# ppgimp.net
KiCad netlist of a schematic drawn in EAGLE
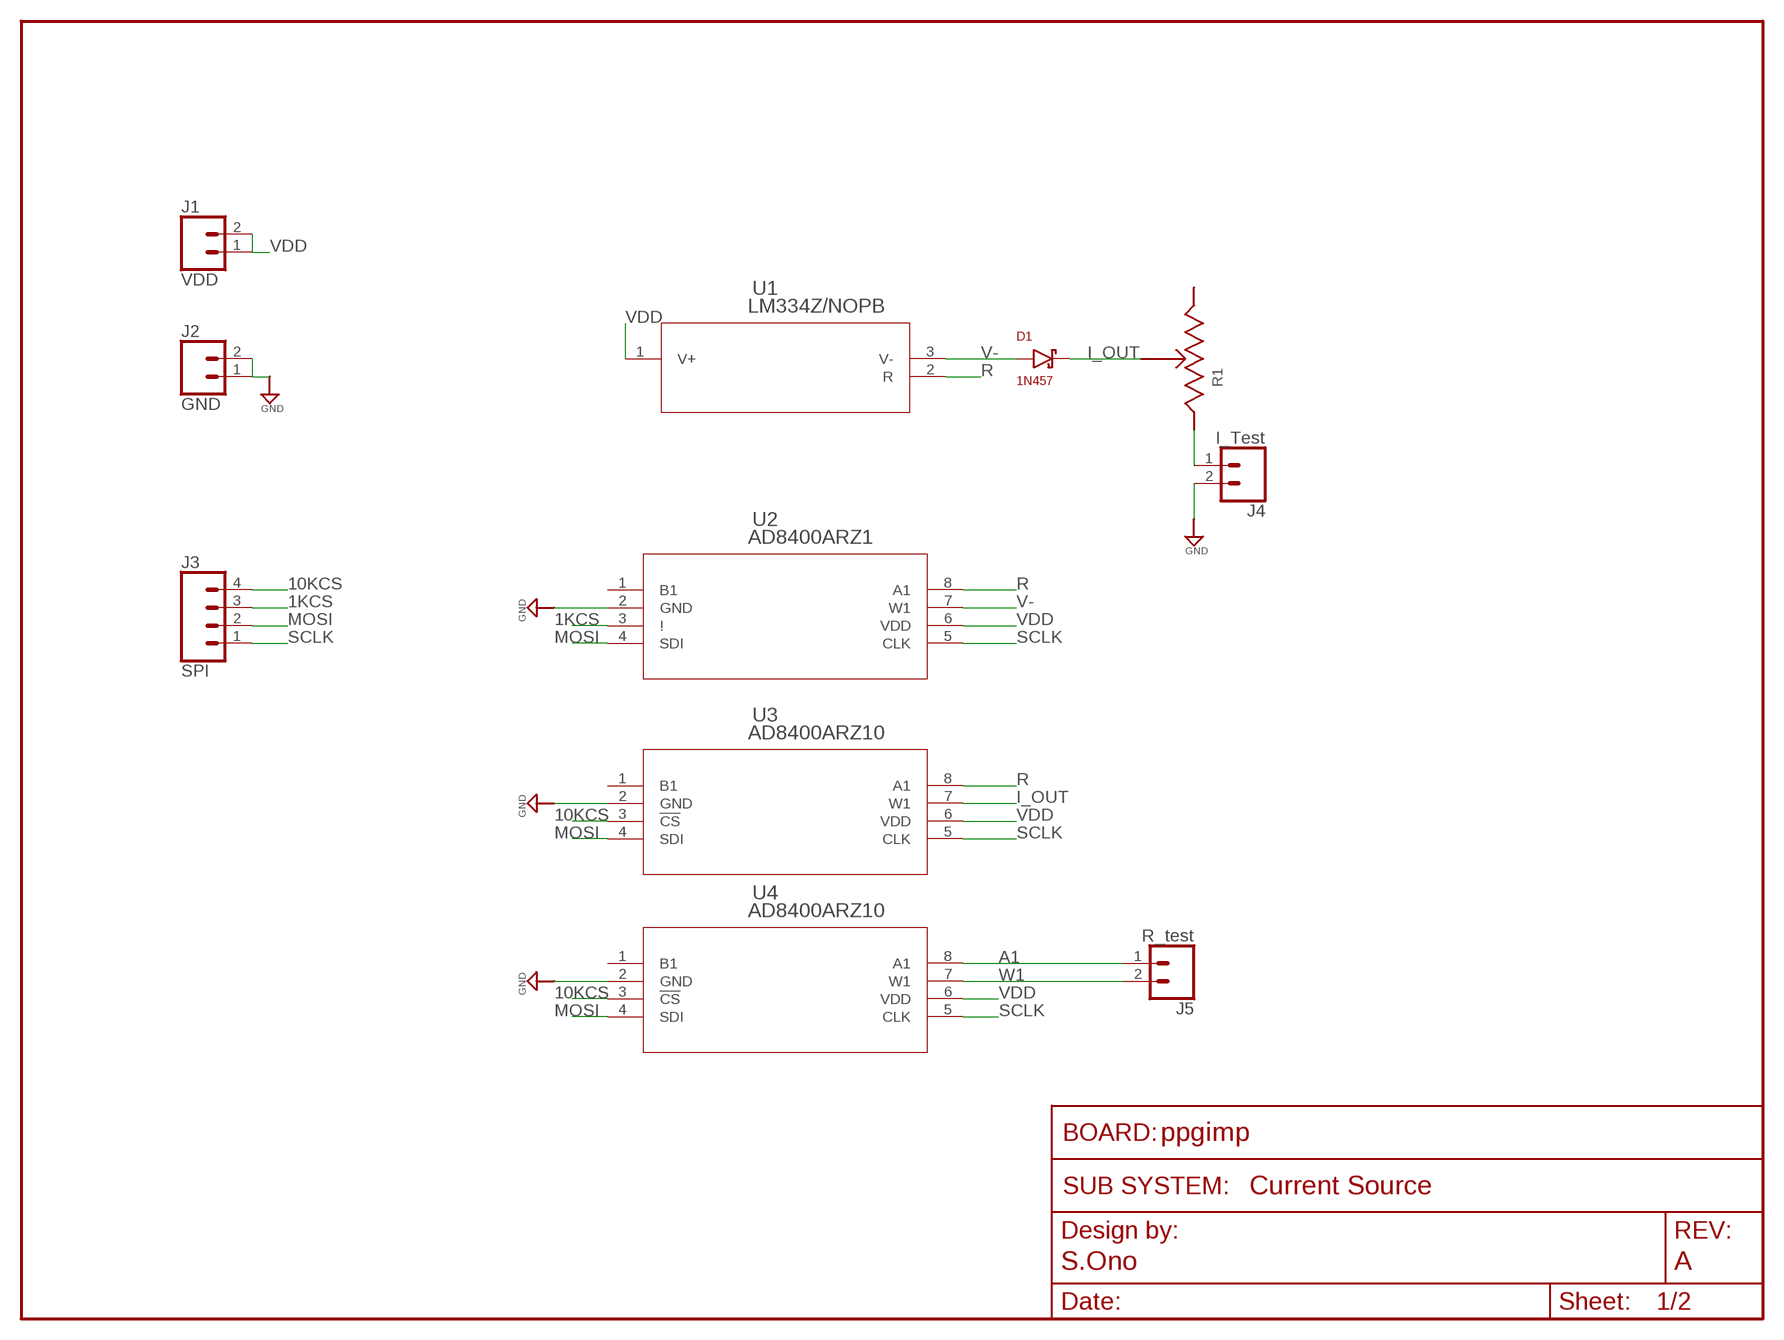
[diagram p0: schematic, sheet 1]
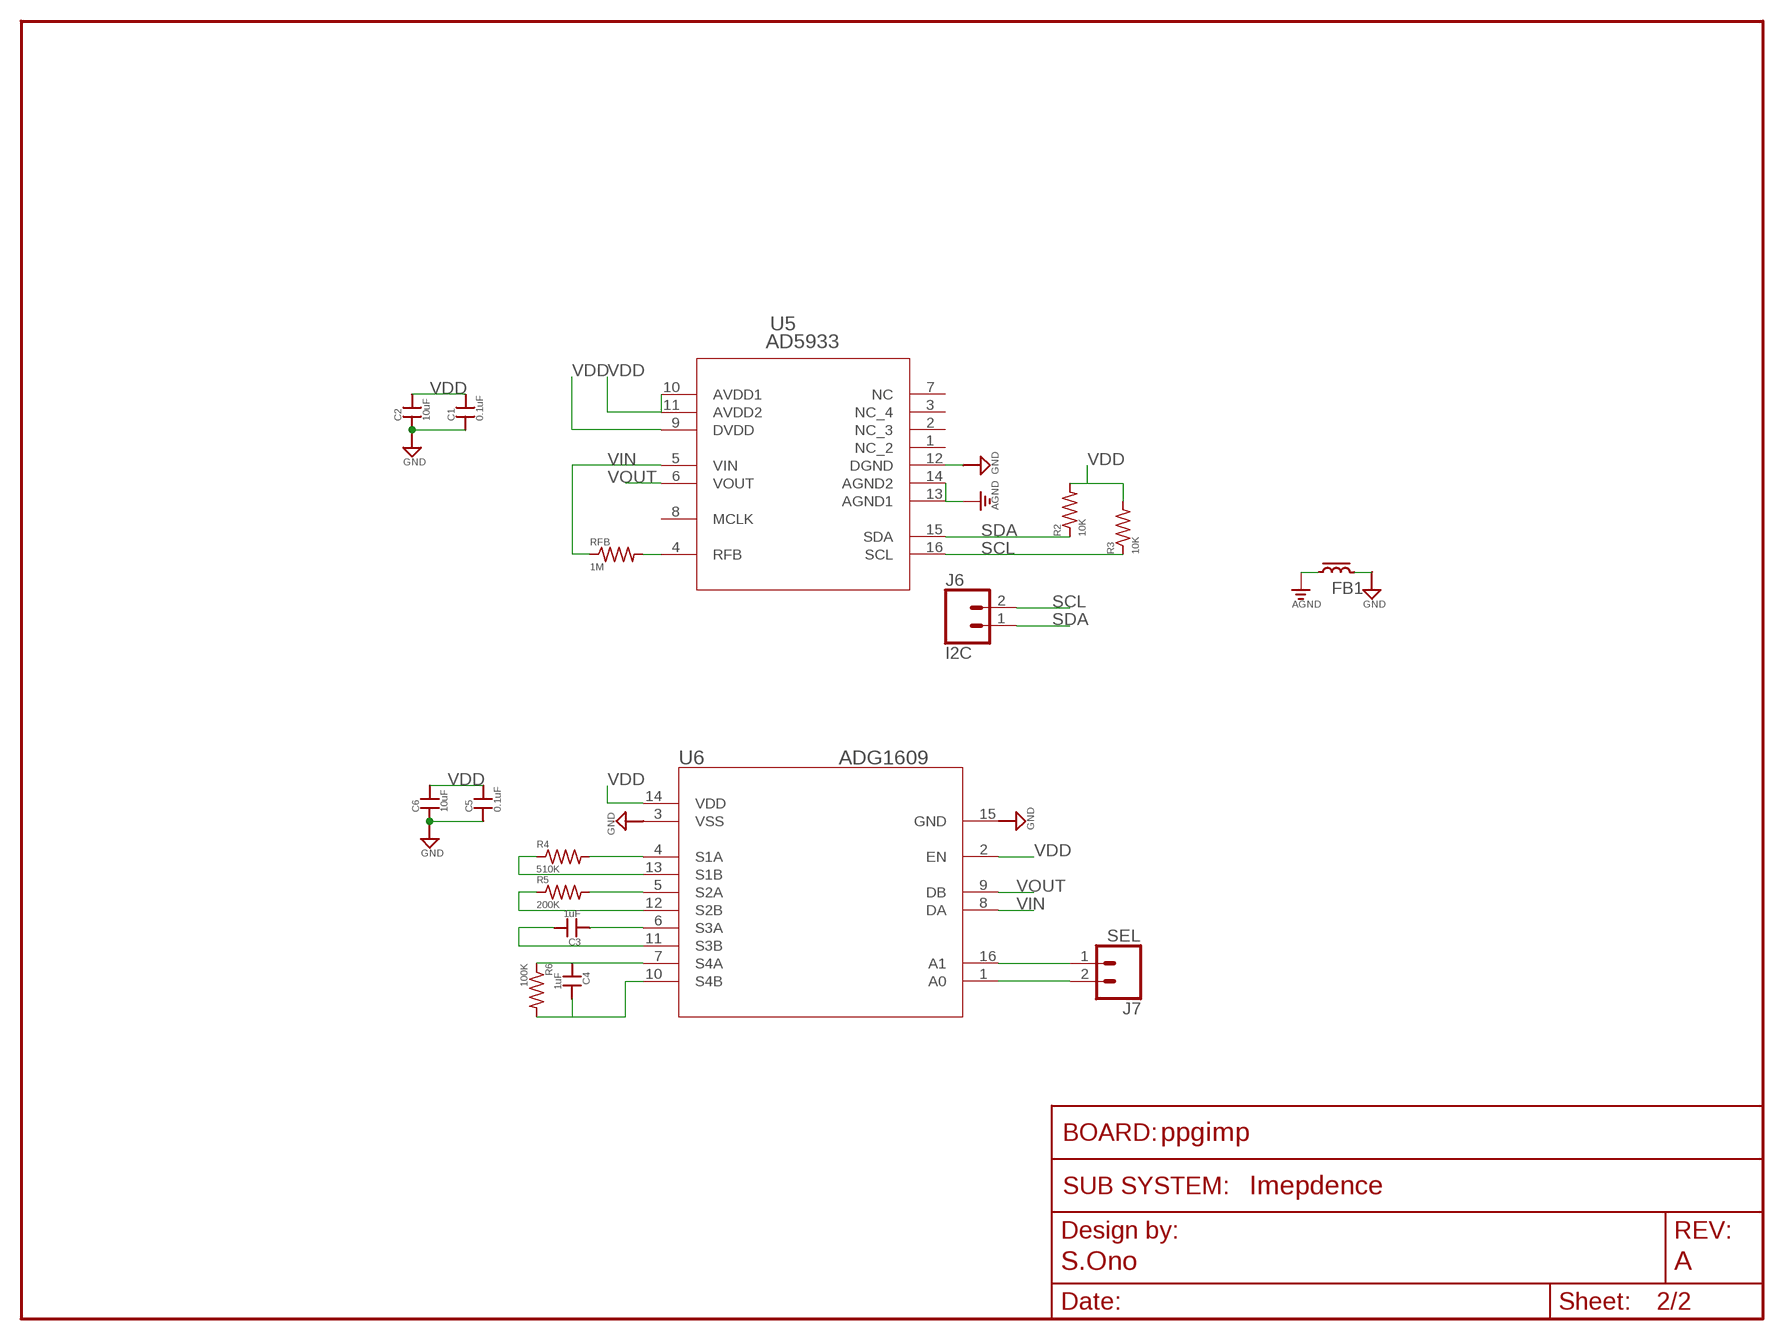
[diagram p1: schematic, sheet 2]

(export (version "E")
  (design (tool "Eeschema 10.0.6"))
  (components
    (comp (ref "C1")
      (value "0.1uF")
      (footprint "eagle-import:0603-CAP")
      (libsource (lib "eagle-import") (part "CAP0603-CAP"))
    )
    (comp (ref "C2")
      (value "10uF")
      (footprint "eagle-import:0603-CAP")
      (libsource (lib "eagle-import") (part "CAP0603-CAP"))
    )
    (comp (ref "C3")
      (value "1uF")
      (footprint "eagle-import:0603-CAP")
      (libsource (lib "eagle-import") (part "CAP0603-CAP"))
    )
    (comp (ref "C4")
      (value "1uF")
      (footprint "eagle-import:0603-CAP")
      (libsource (lib "eagle-import") (part "CAP0603-CAP"))
    )
    (comp (ref "C5")
      (value "0.1uF")
      (footprint "eagle-import:0603-CAP")
      (libsource (lib "eagle-import") (part "CAP0603-CAP"))
    )
    (comp (ref "C6")
      (value "10uF")
      (footprint "eagle-import:0603-CAP")
      (libsource (lib "eagle-import") (part "CAP0603-CAP"))
    )
    (comp (ref "FB1")
      (value "FERRITE")
      (footprint "eagle-import:0603-FERR")
      (libsource (lib "eagle-import") (part "FERRITE"))
    )
    (comp (ref "J6")
      (value "I2C")
      (footprint "eagle-import:1X02")
      (libsource (lib "eagle-import") (part "CONN_02"))
    )
    (comp (ref "J7")
      (value "SEL")
      (footprint "eagle-import:1X02")
      (libsource (lib "eagle-import") (part "CONN_02"))
    )
    (comp (ref "R2")
      (value "10K")
      (footprint "eagle-import:R0603")
      (fields (field (name "MANUFACTURER") "Rohm Semiconductor"))
      (libsource (lib "eagle-import") (part "R-US_R0603"))
    )
    (comp (ref "R3")
      (value "10K")
      (footprint "eagle-import:R0603")
      (fields (field (name "MANUFACTURER") "Rohm Semiconductor"))
      (libsource (lib "eagle-import") (part "R-US_R0603"))
    )
    (comp (ref "R4")
      (value "510K")
      (footprint "eagle-import:R0603")
      (fields (field (name "MANUFACTURER") "Rohm Semiconductor"))
      (libsource (lib "eagle-import") (part "R-US_R0603"))
    )
    (comp (ref "R5")
      (value "200K")
      (footprint "eagle-import:R0603")
      (fields (field (name "MANUFACTURER") "Rohm Semiconductor"))
      (libsource (lib "eagle-import") (part "R-US_R0603"))
    )
    (comp (ref "R6")
      (value "100K")
      (footprint "eagle-import:R0603")
      (fields (field (name "MANUFACTURER") "Rohm Semiconductor"))
      (libsource (lib "eagle-import") (part "R-US_R0603"))
    )
    (comp (ref "RFB")
      (value "1M")
      (footprint "eagle-import:R0603")
      (fields (field (name "MANUFACTURER") "Rohm Semiconductor"))
      (libsource (lib "eagle-import") (part "R-US_R0603"))
    )
    (comp (ref "U5")
      (value "AD5933")
      (footprint "eagle-import:RS_16")
      (fields (field (name "MANUFACTURER_PART_NUMBER") "AD5933YRSZ"))
      (libsource (lib "eagle-import") (part "AD5933YRSZ"))
    )
    (comp (ref "U6")
      (value "ADG1609")
      (footprint "eagle-import:RU_16")
      (fields (field (name "MANUFACTURER_PART_NUMBER") "ADG1609BRUZ"))
      (libsource (lib "eagle-import") (part "ADG1609"))
    )
    (comp (ref "D1")
      (value "1N457")
      (footprint "eagle-import:DIODE_THRU")
      (libsource (lib "eagle-import") (part "1N457"))
    )
    (comp (ref "J1")
      (value "VDD")
      (footprint "eagle-import:1X02")
      (libsource (lib "eagle-import") (part "CONN_02"))
    )
    (comp (ref "J2")
      (value "GND")
      (footprint "eagle-import:1X02")
      (libsource (lib "eagle-import") (part "CONN_02"))
    )
    (comp (ref "J3")
      (value "SPI")
      (footprint "eagle-import:1X04")
      (libsource (lib "eagle-import") (part "CONN_04"))
    )
    (comp (ref "J4")
      (value "I_Test")
      (footprint "eagle-import:1X02")
      (libsource (lib "eagle-import") (part "CONN_02"))
    )
    (comp (ref "J5")
      (value "R_test")
      (footprint "eagle-import:1X02")
      (libsource (lib "eagle-import") (part "CONN_02"))
    )
    (comp (ref "R1")
      (value "POT-3PIN")
      (footprint "eagle-import:POT-3PIN")
      (libsource (lib "eagle-import") (part "POT-3PIN"))
    )
    (comp (ref "U1")
      (value "LM334Z/NOPB")
      (footprint "eagle-import:Z03A")
      (fields (field (name "MANUFACTURER_PART_NUMBER") "LM334ZNOPB"))
      (libsource (lib "eagle-import") (part "LM334Z/NOPB"))
    )
    (comp (ref "U2")
      (value "AD8400ARZ1")
      (footprint "eagle-import:R_8")
      (libsource (lib "eagle-import") (part "AD8400ARZ1"))
    )
    (comp (ref "U3")
      (value "AD8400ARZ10")
      (footprint "eagle-import:R_8")
      (libsource (lib "eagle-import") (part "AD8400ARZ10"))
    )
    (comp (ref "U4")
      (value "AD8400ARZ10")
      (footprint "eagle-import:R_8")
      (libsource (lib "eagle-import") (part "AD8400ARZ10"))
    )
  )
  (nets
    (net (code "1") (name "1KCS") (class "Default")
      (node (ref "J3") (pin "3") (pinfunction "3_3") (pintype "passive"))
      (node (ref "U2") (pin "3") (pinfunction "~_3") (pintype "passive"))
    )
    (net (code "2") (name "10KCS") (class "Default")
      (node (ref "J3") (pin "4") (pinfunction "4_4") (pintype "passive"))
      (node (ref "U3") (pin "3") (pinfunction "~{CS}_3") (pintype "passive"))
      (node (ref "U4") (pin "3") (pinfunction "~{CS}_3") (pintype "passive"))
    )
    (net (code "3") (name "A1") (class "Default")
      (node (ref "J5") (pin "1") (pinfunction "1_1") (pintype "passive"))
      (node (ref "U4") (pin "8") (pinfunction "A1_8") (pintype "passive"))
    )
    (net (code "4") (name "AGND") (class "Default")
      (node (ref "FB1") (pin "1") (pinfunction "P$1_1") (pintype "passive"))
      (node (ref "U5") (pin "13") (pinfunction "AGND1_13") (pintype "passive"))
      (node (ref "U5") (pin "14") (pinfunction "AGND2_14") (pintype "passive"))
    )
    (net (code "5") (name "GND") (class "Default")
      (node (ref "C1") (pin "1") (pinfunction "1_1") (pintype "passive"))
      (node (ref "C2") (pin "1") (pinfunction "1_1") (pintype "passive"))
      (node (ref "C5") (pin "1") (pinfunction "1_1") (pintype "passive"))
      (node (ref "C6") (pin "1") (pinfunction "1_1") (pintype "passive"))
      (node (ref "FB1") (pin "2") (pinfunction "P$2_2") (pintype "passive"))
      (node (ref "J2") (pin "1") (pinfunction "1_1") (pintype "passive"))
      (node (ref "J2") (pin "2") (pinfunction "2_2") (pintype "passive"))
      (node (ref "J4") (pin "2") (pinfunction "2_2") (pintype "passive"))
      (node (ref "U2") (pin "2") (pinfunction "GND_2") (pintype "passive"))
      (node (ref "U3") (pin "2") (pinfunction "GND_2") (pintype "passive"))
      (node (ref "U4") (pin "2") (pinfunction "GND_2") (pintype "passive"))
      (node (ref "U5") (pin "12") (pinfunction "DGND_12") (pintype "passive"))
      (node (ref "U6") (pin "15") (pinfunction "GND_15") (pintype "passive"))
      (node (ref "U6") (pin "3") (pinfunction "VSS_3") (pintype "passive"))
    )
    (net (code "6") (name "I_OUT") (class "Default")
      (node (ref "D1") (pin "2") (pinfunction "N_2") (pintype "bidirectional"))
      (node (ref "R1") (pin "2") (pinfunction "2_2") (pintype "bidirectional"))
      (node (ref "U3") (pin "7") (pinfunction "W1_7") (pintype "passive"))
    )
    (net (code "7") (name "MOSI") (class "Default")
      (node (ref "J3") (pin "2") (pinfunction "2_2") (pintype "passive"))
      (node (ref "U2") (pin "4") (pinfunction "SDI_4") (pintype "passive"))
      (node (ref "U3") (pin "4") (pinfunction "SDI_4") (pintype "passive"))
      (node (ref "U4") (pin "4") (pinfunction "SDI_4") (pintype "passive"))
    )
    (net (code "8") (name "Net-(J4-Pad1)") (class "Default")
      (node (ref "J4") (pin "1") (pinfunction "1_1") (pintype "passive"))
      (node (ref "R1") (pin "3") (pinfunction "3_3") (pintype "bidirectional"))
    )
    (net (code "9") (name "Net-(U5-RFB)") (class "Default")
      (node (ref "RFB") (pin "2") (pinfunction "2_2") (pintype "passive"))
      (node (ref "U5") (pin "4") (pinfunction "RFB_4") (pintype "passive"))
    )
    (net (code "10") (name "Net-(U6-A0)") (class "Default")
      (node (ref "J7") (pin "2") (pinfunction "2_2") (pintype "passive"))
      (node (ref "U6") (pin "1") (pinfunction "A0_1") (pintype "passive"))
    )
    (net (code "11") (name "Net-(U6-A1)") (class "Default")
      (node (ref "J7") (pin "1") (pinfunction "1_1") (pintype "passive"))
      (node (ref "U6") (pin "16") (pinfunction "A1_16") (pintype "passive"))
    )
    (net (code "12") (name "Net-(U6-S1A)") (class "Default")
      (node (ref "R4") (pin "2") (pinfunction "2_2") (pintype "passive"))
      (node (ref "U6") (pin "4") (pinfunction "S1A_4") (pintype "passive"))
    )
    (net (code "13") (name "Net-(U6-S1B)") (class "Default")
      (node (ref "R4") (pin "1") (pinfunction "1_1") (pintype "passive"))
      (node (ref "U6") (pin "13") (pinfunction "S1B_13") (pintype "passive"))
    )
    (net (code "14") (name "Net-(U6-S2A)") (class "Default")
      (node (ref "R5") (pin "2") (pinfunction "2_2") (pintype "passive"))
      (node (ref "U6") (pin "5") (pinfunction "S2A_5") (pintype "passive"))
    )
    (net (code "15") (name "Net-(U6-S2B)") (class "Default")
      (node (ref "R5") (pin "1") (pinfunction "1_1") (pintype "passive"))
      (node (ref "U6") (pin "12") (pinfunction "S2B_12") (pintype "passive"))
    )
    (net (code "16") (name "Net-(U6-S3A)") (class "Default")
      (node (ref "C3") (pin "1") (pinfunction "1_1") (pintype "passive"))
      (node (ref "U6") (pin "6") (pinfunction "S3A_6") (pintype "passive"))
    )
    (net (code "17") (name "Net-(U6-S3B)") (class "Default")
      (node (ref "C3") (pin "2") (pinfunction "2_2") (pintype "passive"))
      (node (ref "U6") (pin "11") (pinfunction "S3B_11") (pintype "passive"))
    )
    (net (code "18") (name "Net-(U6-S4A)") (class "Default")
      (node (ref "C4") (pin "1") (pinfunction "1_1") (pintype "passive"))
      (node (ref "R6") (pin "1") (pinfunction "1_1") (pintype "passive"))
      (node (ref "U6") (pin "7") (pinfunction "S4A_7") (pintype "passive"))
    )
    (net (code "19") (name "Net-(U6-S4B)") (class "Default")
      (node (ref "C4") (pin "2") (pinfunction "2_2") (pintype "passive"))
      (node (ref "R6") (pin "2") (pinfunction "2_2") (pintype "passive"))
      (node (ref "U6") (pin "10") (pinfunction "S4B_10") (pintype "passive"))
    )
    (net (code "20") (name "R") (class "Default")
      (node (ref "U1") (pin "2") (pinfunction "R_2") (pintype "input"))
      (node (ref "U2") (pin "8") (pinfunction "A1_8") (pintype "passive"))
      (node (ref "U3") (pin "8") (pinfunction "A1_8") (pintype "passive"))
    )
    (net (code "21") (name "SCL") (class "Default")
      (node (ref "J6") (pin "2") (pinfunction "2_2") (pintype "passive"))
      (node (ref "R3") (pin "1") (pinfunction "1_1") (pintype "passive"))
      (node (ref "U5") (pin "16") (pinfunction "SCL_16") (pintype "passive"))
    )
    (net (code "22") (name "SCLK") (class "Default")
      (node (ref "J3") (pin "1") (pinfunction "1_1") (pintype "passive"))
      (node (ref "U2") (pin "5") (pinfunction "CLK_5") (pintype "passive"))
      (node (ref "U3") (pin "5") (pinfunction "CLK_5") (pintype "passive"))
      (node (ref "U4") (pin "5") (pinfunction "CLK_5") (pintype "passive"))
    )
    (net (code "23") (name "SDA") (class "Default")
      (node (ref "J6") (pin "1") (pinfunction "1_1") (pintype "passive"))
      (node (ref "R2") (pin "1") (pinfunction "1_1") (pintype "passive"))
      (node (ref "U5") (pin "15") (pinfunction "SDA_15") (pintype "passive"))
    )
    (net (code "24") (name "V-") (class "Default")
      (node (ref "D1") (pin "1") (pinfunction "P_1") (pintype "bidirectional"))
      (node (ref "U1") (pin "3") (pinfunction "V-_3") (pintype "power_in"))
      (node (ref "U2") (pin "7") (pinfunction "W1_7") (pintype "passive"))
    )
    (net (code "25") (name "VDD") (class "Default")
      (node (ref "C1") (pin "2") (pinfunction "2_2") (pintype "passive"))
      (node (ref "C2") (pin "2") (pinfunction "2_2") (pintype "passive"))
      (node (ref "C5") (pin "2") (pinfunction "2_2") (pintype "passive"))
      (node (ref "C6") (pin "2") (pinfunction "2_2") (pintype "passive"))
      (node (ref "J1") (pin "1") (pinfunction "1_1") (pintype "passive"))
      (node (ref "J1") (pin "2") (pinfunction "2_2") (pintype "passive"))
      (node (ref "R2") (pin "2") (pinfunction "2_2") (pintype "passive"))
      (node (ref "R3") (pin "2") (pinfunction "2_2") (pintype "passive"))
      (node (ref "U1") (pin "1") (pinfunction "V+_1") (pintype "power_in"))
      (node (ref "U2") (pin "6") (pinfunction "VDD_6") (pintype "power_in"))
      (node (ref "U3") (pin "6") (pinfunction "VDD_6") (pintype "power_in"))
      (node (ref "U4") (pin "6") (pinfunction "VDD_6") (pintype "power_in"))
      (node (ref "U5") (pin "10") (pinfunction "AVDD1_10") (pintype "passive"))
      (node (ref "U5") (pin "11") (pinfunction "AVDD2_11") (pintype "passive"))
      (node (ref "U5") (pin "9") (pinfunction "DVDD_9") (pintype "passive"))
      (node (ref "U6") (pin "14") (pinfunction "VDD_14") (pintype "passive"))
      (node (ref "U6") (pin "2") (pinfunction "EN_2") (pintype "passive"))
    )
    (net (code "26") (name "VIN") (class "Default")
      (node (ref "RFB") (pin "1") (pinfunction "1_1") (pintype "passive"))
      (node (ref "U5") (pin "5") (pinfunction "VIN_5") (pintype "passive"))
      (node (ref "U6") (pin "8") (pinfunction "DA_8") (pintype "passive"))
    )
    (net (code "27") (name "VOUT") (class "Default")
      (node (ref "U5") (pin "6") (pinfunction "VOUT_6") (pintype "passive"))
      (node (ref "U6") (pin "9") (pinfunction "DB_9") (pintype "passive"))
    )
    (net (code "28") (name "W1") (class "Default")
      (node (ref "J5") (pin "2") (pinfunction "2_2") (pintype "passive"))
      (node (ref "U4") (pin "7") (pinfunction "W1_7") (pintype "passive"))
    )
    (net (code "29") (name "unconnected-(R1-Pad1)") (class "Default")
      (node (ref "R1") (pin "1") (pinfunction "1_1") (pintype "bidirectional"))
    )
    (net (code "30") (name "unconnected-(U2-B1-Pad1)") (class "Default")
      (node (ref "U2") (pin "1") (pinfunction "B1_1") (pintype "passive"))
    )
    (net (code "31") (name "unconnected-(U3-B1-Pad1)") (class "Default")
      (node (ref "U3") (pin "1") (pinfunction "B1_1") (pintype "passive"))
    )
    (net (code "32") (name "unconnected-(U4-B1-Pad1)") (class "Default")
      (node (ref "U4") (pin "1") (pinfunction "B1_1") (pintype "passive"))
    )
    (net (code "33") (name "unconnected-(U5-MCLK-Pad8)") (class "Default")
      (node (ref "U5") (pin "8") (pinfunction "MCLK_8") (pintype "passive"))
    )
    (net (code "34") (name "unconnected-(U5-NC-Pad7)") (class "Default")
      (node (ref "U5") (pin "7") (pinfunction "NC_7") (pintype "passive"))
    )
    (net (code "35") (name "unconnected-(U5-NC_2-Pad1)") (class "Default")
      (node (ref "U5") (pin "1") (pinfunction "NC_2_1") (pintype "passive"))
    )
    (net (code "36") (name "unconnected-(U5-NC_3-Pad2)") (class "Default")
      (node (ref "U5") (pin "2") (pinfunction "NC_3_2") (pintype "passive"))
    )
    (net (code "37") (name "unconnected-(U5-NC_4-Pad3)") (class "Default")
      (node (ref "U5") (pin "3") (pinfunction "NC_4_3") (pintype "passive"))
    )
  )
)
